# 4_82.net
KiCad netlist of a schematic drawn in EasyEDA
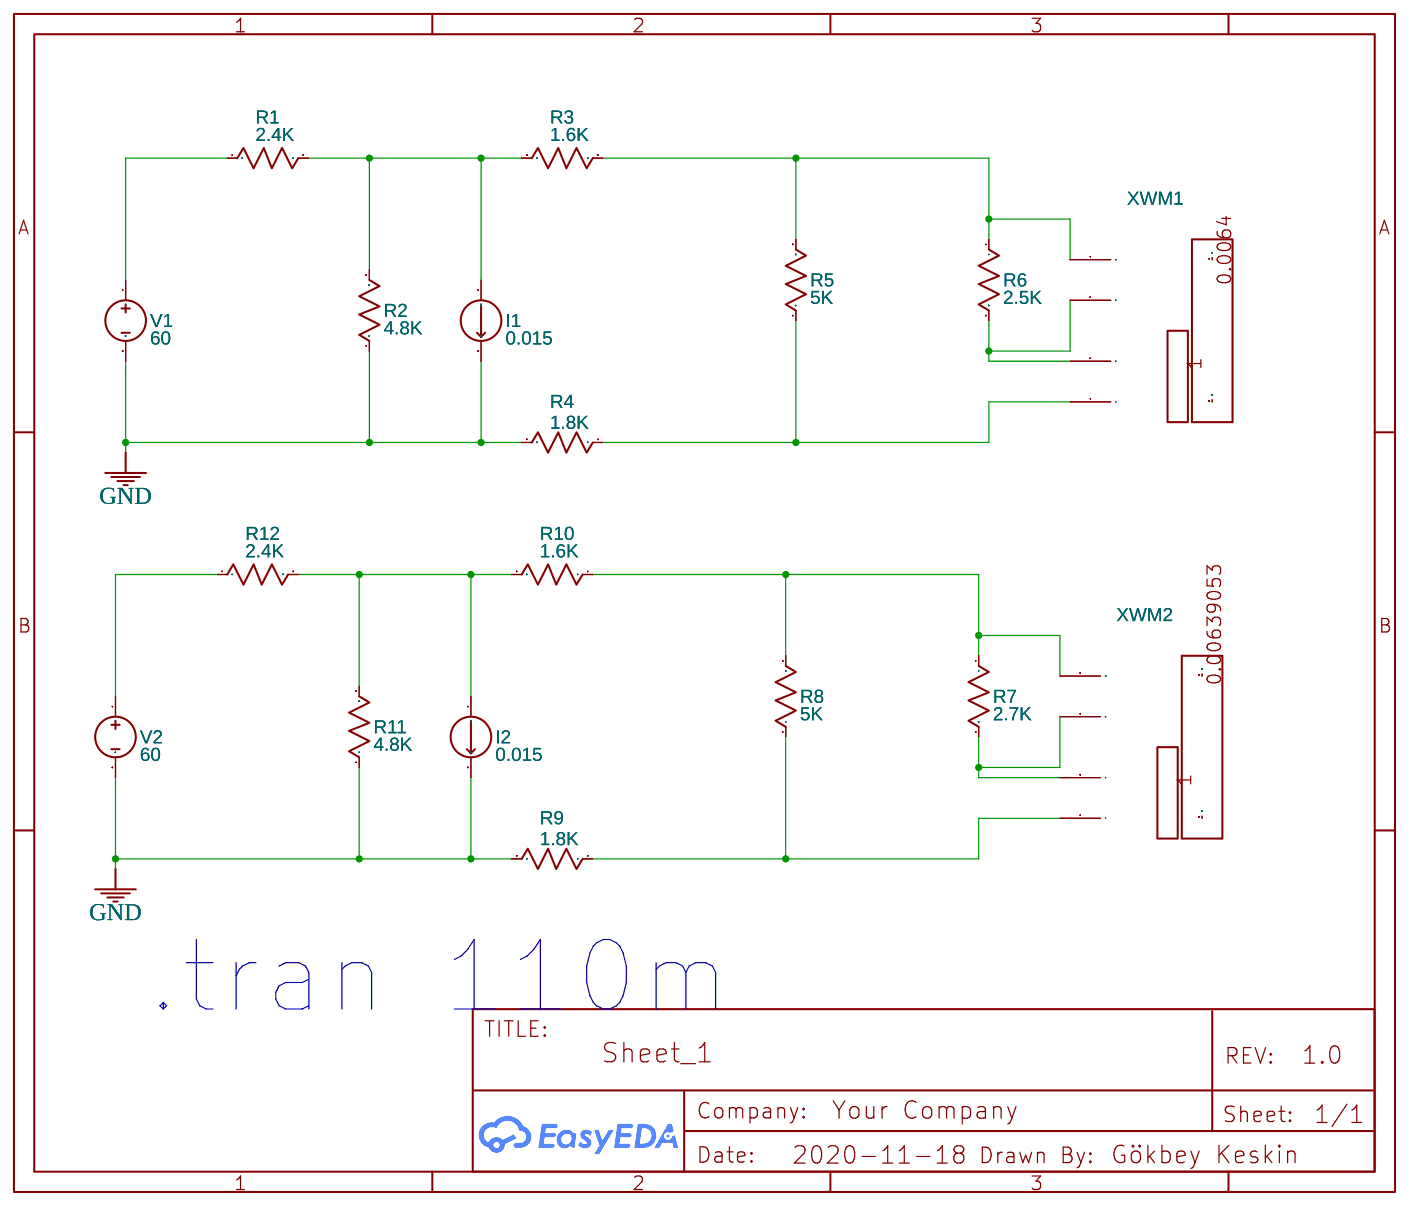
[diagram p0: schematic sheet]

(export (version "E")
  (design (tool "Eeschema 10.0.6"))
  (components
    (comp (ref "I1") (value "0.015") (libsource (lib "") (part "IDC")))
    (comp (ref "I2") (value "0.015") (libsource (lib "") (part "IDC")))
    (comp (ref "R1") (value "2.4K") (libsource (lib "") (part "Resistor_US_3")))
    (comp (ref "R2") (value "4.8K") (libsource (lib "") (part "Resistor_US_2")))
    (comp (ref "R3") (value "1.6K") (libsource (lib "") (part "Resistor_US")))
    (comp (ref "R4") (value "1.8K") (libsource (lib "") (part "Resistor_US")))
    (comp (ref "R5") (value "5K") (libsource (lib "") (part "Resistor_US_2")))
    (comp (ref "R6") (value "2.5K") (libsource (lib "") (part "Resistor_US_1")))
    (comp (ref "R7") (value "2.7K") (libsource (lib "") (part "Resistor_US_1")))
    (comp (ref "R8") (value "5K") (libsource (lib "") (part "Resistor_US_2")))
    (comp (ref "R9") (value "1.8K") (libsource (lib "") (part "Resistor_US")))
    (comp (ref "R10") (value "1.6K") (libsource (lib "") (part "Resistor_US")))
    (comp (ref "R11") (value "4.8K") (libsource (lib "") (part "Resistor_US_2")))
    (comp (ref "R12") (value "2.4K") (libsource (lib "") (part "Resistor_US_3")))
    (comp (ref "V1") (value "60") (libsource (lib "") (part "VDC")))
    (comp (ref "V2") (value "60") (libsource (lib "") (part "VDC")))
    (comp (ref "XWM1") (value "Wattmeter") (libsource (lib "") (part "WATTMETER_1")))
    (comp (ref "XWM2") (value "Wattmeter") (libsource (lib "") (part "WATTMETER")))
  )
  (nets
    (net (code "1") (name "GND") (class "Default")
      (node (ref "I1") (pin "2") (pinfunction "2_2") (pintype "unspecified"))
      (node (ref "I2") (pin "2") (pinfunction "2_2") (pintype "unspecified"))
      (node (ref "R11") (pin "1") (pinfunction "1_1") (pintype "unspecified"))
      (node (ref "R2") (pin "1") (pinfunction "1_1") (pintype "unspecified"))
      (node (ref "R4") (pin "2") (pinfunction "2_2") (pintype "unspecified"))
      (node (ref "R9") (pin "2") (pinfunction "2_2") (pintype "unspecified"))
      (node (ref "V1") (pin "2") (pinfunction "2_2") (pintype "unspecified"))
      (node (ref "V2") (pin "2") (pinfunction "2_2") (pintype "unspecified"))
    )
    (net (code "2") (name "Net-(I1-Pad1)") (class "Default")
      (node (ref "I1") (pin "1") (pinfunction "1_1") (pintype "unspecified"))
      (node (ref "R1") (pin "2") (pinfunction "2_2") (pintype "unspecified"))
      (node (ref "R2") (pin "2") (pinfunction "2_2") (pintype "unspecified"))
      (node (ref "R3") (pin "2") (pinfunction "2_2") (pintype "unspecified"))
    )
    (net (code "3") (name "Net-(I2-Pad1)") (class "Default")
      (node (ref "I2") (pin "1") (pinfunction "1_1") (pintype "unspecified"))
      (node (ref "R10") (pin "2") (pinfunction "2_2") (pintype "unspecified"))
      (node (ref "R11") (pin "2") (pinfunction "2_2") (pintype "unspecified"))
      (node (ref "R12") (pin "2") (pinfunction "2_2") (pintype "unspecified"))
    )
    (net (code "4") (name "Net-(R1-Pad1)") (class "Default")
      (node (ref "R1") (pin "1") (pinfunction "1_1") (pintype "unspecified"))
      (node (ref "V1") (pin "1") (pinfunction "1_1") (pintype "unspecified"))
    )
    (net (code "5") (name "Net-(R12-Pad1)") (class "Default")
      (node (ref "R12") (pin "1") (pinfunction "1_1") (pintype "unspecified"))
      (node (ref "V2") (pin "1") (pinfunction "1_1") (pintype "unspecified"))
    )
    (net (code "6") (name "Net-(XWM1-I+)") (class "Default")
      (node (ref "R6") (pin "2") (pinfunction "2_2") (pintype "unspecified"))
      (node (ref "XWM1") (pin "2") (pinfunction "V-_2") (pintype "unspecified"))
      (node (ref "XWM1") (pin "3") (pinfunction "I+_3") (pintype "unspecified"))
    )
    (net (code "7") (name "Net-(XWM1-I-)") (class "Default")
      (node (ref "R4") (pin "1") (pinfunction "1_1") (pintype "unspecified"))
      (node (ref "R5") (pin "1") (pinfunction "1_1") (pintype "unspecified"))
      (node (ref "XWM1") (pin "4") (pinfunction "I-_4") (pintype "unspecified"))
    )
    (net (code "8") (name "Net-(XWM1-V+)") (class "Default")
      (node (ref "R3") (pin "1") (pinfunction "1_1") (pintype "unspecified"))
      (node (ref "R5") (pin "2") (pinfunction "2_2") (pintype "unspecified"))
      (node (ref "R6") (pin "1") (pinfunction "1_1") (pintype "unspecified"))
      (node (ref "XWM1") (pin "1") (pinfunction "V+_1") (pintype "unspecified"))
    )
    (net (code "9") (name "Net-(XWM2-I+)") (class "Default")
      (node (ref "R7") (pin "2") (pinfunction "2_2") (pintype "unspecified"))
      (node (ref "XWM2") (pin "2") (pinfunction "V-_2") (pintype "unspecified"))
      (node (ref "XWM2") (pin "3") (pinfunction "I+_3") (pintype "unspecified"))
    )
    (net (code "10") (name "Net-(XWM2-I-)") (class "Default")
      (node (ref "R8") (pin "1") (pinfunction "1_1") (pintype "unspecified"))
      (node (ref "R9") (pin "1") (pinfunction "1_1") (pintype "unspecified"))
      (node (ref "XWM2") (pin "4") (pinfunction "I-_4") (pintype "unspecified"))
    )
    (net (code "11") (name "Net-(XWM2-V+)") (class "Default")
      (node (ref "R10") (pin "1") (pinfunction "1_1") (pintype "unspecified"))
      (node (ref "R7") (pin "1") (pinfunction "1_1") (pintype "unspecified"))
      (node (ref "R8") (pin "2") (pinfunction "2_2") (pintype "unspecified"))
      (node (ref "XWM2") (pin "1") (pinfunction "V+_1") (pintype "unspecified"))
    )
    (net (code "12") (name "unconnected-(XWM1-PadP)") (class "Default")
      (node (ref "XWM1") (pin "P") (pinfunction "P_P") (pintype "unspecified"))
    )
    (net (code "13") (name "unconnected-(XWM1-PadPF)") (class "Default")
      (node (ref "XWM1") (pin "PF") (pinfunction "PF_PF") (pintype "unspecified"))
    )
    (net (code "14") (name "unconnected-(XWM2-PadP)") (class "Default")
      (node (ref "XWM2") (pin "P") (pinfunction "P_P") (pintype "unspecified"))
    )
    (net (code "15") (name "unconnected-(XWM2-PadPF)") (class "Default")
      (node (ref "XWM2") (pin "PF") (pinfunction "PF_PF") (pintype "unspecified"))
    )
  )
)
